# Hitachi100NZ.net
KiCad netlist of a schematic drawn in Altium Designer
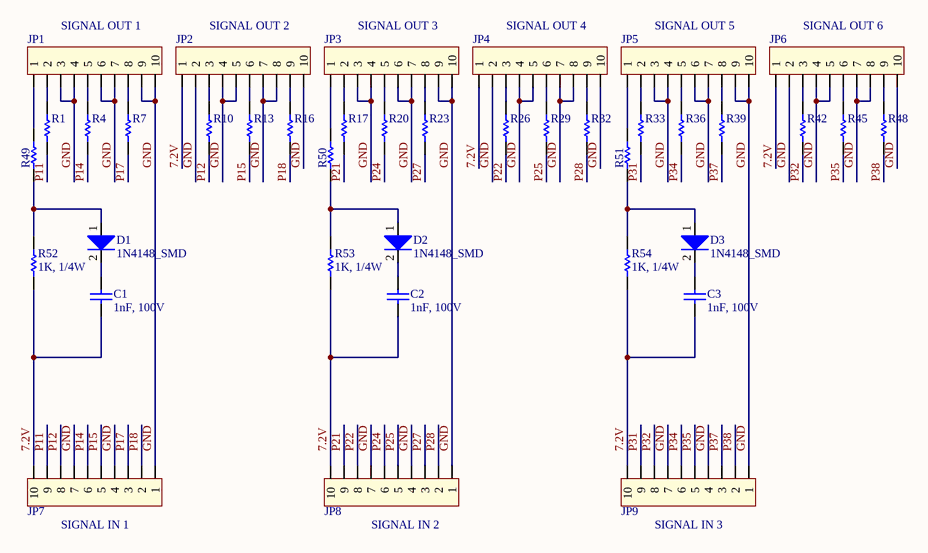
[diagram p0: Hitachi100NZ.SchDoc]

(export (version "E")
  (design (tool "Eeschema 10.0.6"))
  (components
    (comp (ref "C1")
      (value "1nF, 100V")
      (footprint "C0603")
      (description "CAP NPO CAPNTO 1nF 100V 10%")
      (fields (field (name "Comment") "5AK102KABAA"))
      (libsource (lib "lpson") (part "5AK102KABAA"))
    )
    (comp (ref "C2")
      (value "1nF, 100V")
      (footprint "C0603")
      (description "CAP NPO CAPNTO 1nF 100V 10%")
      (fields (field (name "Comment") "5AK102KABAA"))
      (libsource (lib "lpson") (part "5AK102KABAA"))
    )
    (comp (ref "C3")
      (value "1nF, 100V")
      (footprint "C0603")
      (description "CAP NPO CAPNTO 1nF 100V 10%")
      (fields (field (name "Comment") "5AK102KABAA"))
      (libsource (lib "lpson") (part "5AK102KABAA"))
    )
    (comp (ref "D1")
      (value "1N4148_SMD")
      (footprint "1N4148W_V_SMD")
      (description "Diode HS 500mA 100V SOD123")
      (libsource (lib "lpson") (part "1N4148_SMD"))
    )
    (comp (ref "D2")
      (value "1N4148_SMD")
      (footprint "1N4148W_V_SMD")
      (description "Diode HS 500mA 100V SOD123")
      (libsource (lib "lpson") (part "1N4148_SMD"))
    )
    (comp (ref "D3")
      (value "1N4148_SMD")
      (footprint "1N4148W_V_SMD")
      (description "Diode HS 500mA 100V SOD123")
      (libsource (lib "lpson") (part "1N4148_SMD"))
    )
    (comp (ref "JP1")
      (value "SIGNAL OUT 1")
      (footprint "HeaderSP_5x2")
      (description "Connector 10")
      (libsource (lib "") (part "Con10_1"))
    )
    (comp (ref "JP2")
      (value "SIGNAL OUT 2")
      (footprint "HeaderSP_5x2")
      (description "Connector 10")
      (libsource (lib "") (part "Con10_1"))
    )
    (comp (ref "JP3")
      (value "SIGNAL OUT 3")
      (footprint "HeaderSP_5x2")
      (description "Connector 10")
      (libsource (lib "") (part "Con10_1"))
    )
    (comp (ref "JP4")
      (value "SIGNAL OUT 4")
      (footprint "HeaderSP_5x2")
      (description "Connector 10")
      (libsource (lib "") (part "Con10_1"))
    )
    (comp (ref "JP5")
      (value "SIGNAL OUT 5")
      (footprint "HeaderSP_5x2")
      (description "Connector 10")
      (libsource (lib "") (part "Con10_1"))
    )
    (comp (ref "JP6")
      (value "SIGNAL OUT 6")
      (footprint "HeaderSP_5x2")
      (description "Connector 10")
      (libsource (lib "") (part "Con10_1"))
    )
    (comp (ref "JP7")
      (value "SIGNAL IN 1")
      (footprint "HeaderSP_5x2")
      (description "Connector 10")
      (libsource (lib "lpson") (part "Con10"))
    )
    (comp (ref "JP8")
      (value "SIGNAL IN 2")
      (footprint "HeaderSP_5x2")
      (description "Connector 10")
      (libsource (lib "lpson") (part "Con10"))
    )
    (comp (ref "JP9")
      (value "SIGNAL IN 3")
      (footprint "HeaderSP_5x2")
      (description "Connector 10")
      (libsource (lib "lpson") (part "Con10"))
    )
    (comp (ref "R1")
      (value "CF1/4W1KJ25")
      (footprint "RM06JTN (0603)")
      (description "RES CF AXIAL-0.3 5% 1/4W 1K")
      (libsource (lib "lpson") (part "CF1/4W1KJ25"))
    )
    (comp (ref "R4")
      (value "CF1/4W1KJ25")
      (footprint "RM06JTN (0603)")
      (description "RES CF AXIAL-0.3 5% 1/4W 1K")
      (libsource (lib "lpson") (part "CF1/4W1KJ25"))
    )
    (comp (ref "R7")
      (value "CF1/4W1KJ25")
      (footprint "RM06JTN (0603)")
      (description "RES CF AXIAL-0.3 5% 1/4W 1K")
      (libsource (lib "lpson") (part "CF1/4W1KJ25"))
    )
    (comp (ref "R10")
      (value "CF1/4W1KJ25")
      (footprint "RM06JTN (0603)")
      (description "RES CF AXIAL-0.3 5% 1/4W 1K")
      (libsource (lib "lpson") (part "CF1/4W1KJ25"))
    )
    (comp (ref "R13")
      (value "CF1/4W1KJ25")
      (footprint "RM06JTN (0603)")
      (description "RES CF AXIAL-0.3 5% 1/4W 1K")
      (libsource (lib "lpson") (part "CF1/4W1KJ25"))
    )
    (comp (ref "R16")
      (value "CF1/4W1KJ25")
      (footprint "RM06JTN (0603)")
      (description "RES CF AXIAL-0.3 5% 1/4W 1K")
      (libsource (lib "lpson") (part "CF1/4W1KJ25"))
    )
    (comp (ref "R17")
      (value "CF1/4W1KJ25")
      (footprint "RM06JTN (0603)")
      (description "RES CF AXIAL-0.3 5% 1/4W 1K")
      (libsource (lib "lpson") (part "CF1/4W1KJ25"))
    )
    (comp (ref "R20")
      (value "CF1/4W1KJ25")
      (footprint "RM06JTN (0603)")
      (description "RES CF AXIAL-0.3 5% 1/4W 1K")
      (libsource (lib "lpson") (part "CF1/4W1KJ25"))
    )
    (comp (ref "R23")
      (value "CF1/4W1KJ25")
      (footprint "RM06JTN (0603)")
      (description "RES CF AXIAL-0.3 5% 1/4W 1K")
      (libsource (lib "lpson") (part "CF1/4W1KJ25"))
    )
    (comp (ref "R26")
      (value "CF1/4W1KJ25")
      (footprint "RM06JTN (0603)")
      (description "RES CF AXIAL-0.3 5% 1/4W 1K")
      (libsource (lib "lpson") (part "CF1/4W1KJ25"))
    )
    (comp (ref "R29")
      (value "CF1/4W1KJ25")
      (footprint "RM06JTN (0603)")
      (description "RES CF AXIAL-0.3 5% 1/4W 1K")
      (libsource (lib "lpson") (part "CF1/4W1KJ25"))
    )
    (comp (ref "R32")
      (value "CF1/4W1KJ25")
      (footprint "RM06JTN (0603)")
      (description "RES CF AXIAL-0.3 5% 1/4W 1K")
      (libsource (lib "lpson") (part "CF1/4W1KJ25"))
    )
    (comp (ref "R33")
      (value "CF1/4W1KJ25")
      (footprint "RM06JTN (0603)")
      (description "RES CF AXIAL-0.3 5% 1/4W 1K")
      (libsource (lib "lpson") (part "CF1/4W1KJ25"))
    )
    (comp (ref "R36")
      (value "CF1/4W1KJ25")
      (footprint "RM06JTN (0603)")
      (description "RES CF AXIAL-0.3 5% 1/4W 1K")
      (libsource (lib "lpson") (part "CF1/4W1KJ25"))
    )
    (comp (ref "R39")
      (value "CF1/4W1KJ25")
      (footprint "RM06JTN (0603)")
      (description "RES CF AXIAL-0.3 5% 1/4W 1K")
      (libsource (lib "lpson") (part "CF1/4W1KJ25"))
    )
    (comp (ref "R42")
      (value "CF1/4W1KJ25")
      (footprint "RM06JTN (0603)")
      (description "RES CF AXIAL-0.3 5% 1/4W 1K")
      (libsource (lib "lpson") (part "CF1/4W1KJ25"))
    )
    (comp (ref "R45")
      (value "CF1/4W1KJ25")
      (footprint "RM06JTN (0603)")
      (description "RES CF AXIAL-0.3 5% 1/4W 1K")
      (libsource (lib "lpson") (part "CF1/4W1KJ25"))
    )
    (comp (ref "R48")
      (value "CF1/4W1KJ25")
      (footprint "RM06JTN (0603)")
      (description "RES CF AXIAL-0.3 5% 1/4W 1K")
      (libsource (lib "lpson") (part "CF1/4W1KJ25"))
    )
    (comp (ref "R49")
      (value "CF1/4W1KJ25")
      (footprint "RM06JTN (0603)")
      (description "RES CF AXIAL-0.3 5% 1/4W 1K")
      (libsource (lib "lpson") (part "CF1/4W1KJ25"))
    )
    (comp (ref "R50")
      (value "CF1/4W1KJ25")
      (footprint "RM06JTN (0603)")
      (description "RES CF AXIAL-0.3 5% 1/4W 1K")
      (libsource (lib "lpson") (part "CF1/4W1KJ25"))
    )
    (comp (ref "R51")
      (value "CF1/4W1KJ25")
      (footprint "RM06JTN (0603)")
      (description "RES CF AXIAL-0.3 5% 1/4W 1K")
      (libsource (lib "lpson") (part "CF1/4W1KJ25"))
    )
    (comp (ref "R52")
      (value "1K, 1/4W")
      (footprint "RM06JTN (0603)")
      (description "RES CF AXIAL-0.3 5% 1/4W 1K")
      (fields (field (name "Comment") "CF1/4W1KJ25"))
      (libsource (lib "lpson") (part "CF1/4W1KJ25"))
    )
    (comp (ref "R53")
      (value "1K, 1/4W")
      (footprint "RM06JTN (0603)")
      (description "RES CF AXIAL-0.3 5% 1/4W 1K")
      (fields (field (name "Comment") "CF1/4W1KJ25"))
      (libsource (lib "lpson") (part "CF1/4W1KJ25"))
    )
    (comp (ref "R54")
      (value "1K, 1/4W")
      (footprint "RM06JTN (0603)")
      (description "RES CF AXIAL-0.3 5% 1/4W 1K")
      (fields (field (name "Comment") "CF1/4W1KJ25"))
      (libsource (lib "lpson") (part "CF1/4W1KJ25"))
    )
  )
  (nets
    (net (code "1") (name "/7.2V") (class "Default")
      (node (ref "C1") (pin "1") (pinfunction "1_1") (pintype "passive"))
      (node (ref "C2") (pin "1") (pinfunction "1_1") (pintype "passive"))
      (node (ref "C3") (pin "1") (pinfunction "1_1") (pintype "passive"))
      (node (ref "JP2") (pin "1") (pinfunction "1_1") (pintype "passive"))
      (node (ref "JP4") (pin "1") (pinfunction "1_1") (pintype "passive"))
      (node (ref "JP6") (pin "1") (pinfunction "1_1") (pintype "passive"))
      (node (ref "JP7") (pin "10") (pinfunction "10_10") (pintype "passive"))
      (node (ref "JP8") (pin "10") (pinfunction "10_10") (pintype "passive"))
      (node (ref "JP9") (pin "10") (pinfunction "10_10") (pintype "passive"))
      (node (ref "R52") (pin "1") (pinfunction "1_1") (pintype "passive"))
      (node (ref "R53") (pin "1") (pinfunction "1_1") (pintype "passive"))
      (node (ref "R54") (pin "1") (pinfunction "1_1") (pintype "passive"))
    )
    (net (code "2") (name "/GND") (class "Default")
      (node (ref "JP1") (pin "10") (pinfunction "10_10") (pintype "passive"))
      (node (ref "JP1") (pin "3") (pinfunction "3_3") (pintype "passive"))
      (node (ref "JP1") (pin "4") (pinfunction "4_4") (pintype "passive"))
      (node (ref "JP1") (pin "6") (pinfunction "6_6") (pintype "passive"))
      (node (ref "JP1") (pin "7") (pinfunction "7_7") (pintype "passive"))
      (node (ref "JP1") (pin "9") (pinfunction "9_9") (pintype "passive"))
      (node (ref "JP2") (pin "10") (pinfunction "10_10") (pintype "passive"))
      (node (ref "JP2") (pin "2") (pinfunction "2_2") (pintype "passive"))
      (node (ref "JP2") (pin "4") (pinfunction "4_4") (pintype "passive"))
      (node (ref "JP2") (pin "5") (pinfunction "5_5") (pintype "passive"))
      (node (ref "JP2") (pin "7") (pinfunction "7_7") (pintype "passive"))
      (node (ref "JP2") (pin "8") (pinfunction "8_8") (pintype "passive"))
      (node (ref "JP3") (pin "10") (pinfunction "10_10") (pintype "passive"))
      (node (ref "JP3") (pin "3") (pinfunction "3_3") (pintype "passive"))
      (node (ref "JP3") (pin "4") (pinfunction "4_4") (pintype "passive"))
      (node (ref "JP3") (pin "6") (pinfunction "6_6") (pintype "passive"))
      (node (ref "JP3") (pin "7") (pinfunction "7_7") (pintype "passive"))
      (node (ref "JP3") (pin "9") (pinfunction "9_9") (pintype "passive"))
      (node (ref "JP4") (pin "10") (pinfunction "10_10") (pintype "passive"))
      (node (ref "JP4") (pin "2") (pinfunction "2_2") (pintype "passive"))
      (node (ref "JP4") (pin "4") (pinfunction "4_4") (pintype "passive"))
      (node (ref "JP4") (pin "5") (pinfunction "5_5") (pintype "passive"))
      (node (ref "JP4") (pin "7") (pinfunction "7_7") (pintype "passive"))
      (node (ref "JP4") (pin "8") (pinfunction "8_8") (pintype "passive"))
      (node (ref "JP5") (pin "10") (pinfunction "10_10") (pintype "passive"))
      (node (ref "JP5") (pin "3") (pinfunction "3_3") (pintype "passive"))
      (node (ref "JP5") (pin "4") (pinfunction "4_4") (pintype "passive"))
      (node (ref "JP5") (pin "6") (pinfunction "6_6") (pintype "passive"))
      (node (ref "JP5") (pin "7") (pinfunction "7_7") (pintype "passive"))
      (node (ref "JP5") (pin "9") (pinfunction "9_9") (pintype "passive"))
      (node (ref "JP6") (pin "10") (pinfunction "10_10") (pintype "passive"))
      (node (ref "JP6") (pin "2") (pinfunction "2_2") (pintype "passive"))
      (node (ref "JP6") (pin "4") (pinfunction "4_4") (pintype "passive"))
      (node (ref "JP6") (pin "5") (pinfunction "5_5") (pintype "passive"))
      (node (ref "JP6") (pin "7") (pinfunction "7_7") (pintype "passive"))
      (node (ref "JP6") (pin "8") (pinfunction "8_8") (pintype "passive"))
      (node (ref "JP7") (pin "1") (pinfunction "1_1") (pintype "passive"))
      (node (ref "JP7") (pin "4") (pinfunction "4_4") (pintype "passive"))
      (node (ref "JP7") (pin "7") (pinfunction "7_7") (pintype "passive"))
      (node (ref "JP8") (pin "1") (pinfunction "1_1") (pintype "passive"))
      (node (ref "JP8") (pin "4") (pinfunction "4_4") (pintype "passive"))
      (node (ref "JP8") (pin "7") (pinfunction "7_7") (pintype "passive"))
      (node (ref "JP9") (pin "1") (pinfunction "1_1") (pintype "passive"))
      (node (ref "JP9") (pin "4") (pinfunction "4_4") (pintype "passive"))
      (node (ref "JP9") (pin "7") (pinfunction "7_7") (pintype "passive"))
    )
    (net (code "3") (name "/P11") (class "Default")
      (node (ref "JP7") (pin "9") (pinfunction "9_9") (pintype "passive"))
      (node (ref "R1") (pin "1") (pinfunction "1_1") (pintype "passive"))
    )
    (net (code "4") (name "/P12") (class "Default")
      (node (ref "JP7") (pin "8") (pinfunction "8_8") (pintype "passive"))
      (node (ref "R10") (pin "1") (pinfunction "1_1") (pintype "passive"))
    )
    (net (code "5") (name "/P14") (class "Default")
      (node (ref "JP7") (pin "6") (pinfunction "6_6") (pintype "passive"))
      (node (ref "R4") (pin "1") (pinfunction "1_1") (pintype "passive"))
    )
    (net (code "6") (name "/P15") (class "Default")
      (node (ref "JP7") (pin "5") (pinfunction "5_5") (pintype "passive"))
      (node (ref "R13") (pin "1") (pinfunction "1_1") (pintype "passive"))
    )
    (net (code "7") (name "/P17") (class "Default")
      (node (ref "JP7") (pin "3") (pinfunction "3_3") (pintype "passive"))
      (node (ref "R7") (pin "1") (pinfunction "1_1") (pintype "passive"))
    )
    (net (code "8") (name "/P18") (class "Default")
      (node (ref "JP7") (pin "2") (pinfunction "2_2") (pintype "passive"))
      (node (ref "R16") (pin "1") (pinfunction "1_1") (pintype "passive"))
    )
    (net (code "9") (name "/P21") (class "Default")
      (node (ref "JP8") (pin "9") (pinfunction "9_9") (pintype "passive"))
      (node (ref "R17") (pin "1") (pinfunction "1_1") (pintype "passive"))
    )
    (net (code "10") (name "/P22") (class "Default")
      (node (ref "JP8") (pin "8") (pinfunction "8_8") (pintype "passive"))
      (node (ref "R26") (pin "1") (pinfunction "1_1") (pintype "passive"))
    )
    (net (code "11") (name "/P24") (class "Default")
      (node (ref "JP8") (pin "6") (pinfunction "6_6") (pintype "passive"))
      (node (ref "R20") (pin "1") (pinfunction "1_1") (pintype "passive"))
    )
    (net (code "12") (name "/P25") (class "Default")
      (node (ref "JP8") (pin "5") (pinfunction "5_5") (pintype "passive"))
      (node (ref "R29") (pin "1") (pinfunction "1_1") (pintype "passive"))
    )
    (net (code "13") (name "/P27") (class "Default")
      (node (ref "JP8") (pin "3") (pinfunction "3_3") (pintype "passive"))
      (node (ref "R23") (pin "1") (pinfunction "1_1") (pintype "passive"))
    )
    (net (code "14") (name "/P28") (class "Default")
      (node (ref "JP8") (pin "2") (pinfunction "2_2") (pintype "passive"))
      (node (ref "R32") (pin "1") (pinfunction "1_1") (pintype "passive"))
    )
    (net (code "15") (name "/P31") (class "Default")
      (node (ref "JP9") (pin "9") (pinfunction "9_9") (pintype "passive"))
      (node (ref "R33") (pin "1") (pinfunction "1_1") (pintype "passive"))
    )
    (net (code "16") (name "/P32") (class "Default")
      (node (ref "JP9") (pin "8") (pinfunction "8_8") (pintype "passive"))
      (node (ref "R42") (pin "1") (pinfunction "1_1") (pintype "passive"))
    )
    (net (code "17") (name "/P34") (class "Default")
      (node (ref "JP9") (pin "6") (pinfunction "6_6") (pintype "passive"))
      (node (ref "R36") (pin "1") (pinfunction "1_1") (pintype "passive"))
    )
    (net (code "18") (name "/P35") (class "Default")
      (node (ref "JP9") (pin "5") (pinfunction "5_5") (pintype "passive"))
      (node (ref "R45") (pin "1") (pinfunction "1_1") (pintype "passive"))
    )
    (net (code "19") (name "/P37") (class "Default")
      (node (ref "JP9") (pin "3") (pinfunction "3_3") (pintype "passive"))
      (node (ref "R39") (pin "1") (pinfunction "1_1") (pintype "passive"))
    )
    (net (code "20") (name "/P38") (class "Default")
      (node (ref "JP9") (pin "2") (pinfunction "2_2") (pintype "passive"))
      (node (ref "R48") (pin "1") (pinfunction "1_1") (pintype "passive"))
    )
    (net (code "21") (name "Net-(D1-A)") (class "Default")
      (node (ref "D1") (pin "1") (pinfunction "A_1") (pintype "passive"))
      (node (ref "R49") (pin "1") (pinfunction "1_1") (pintype "passive"))
      (node (ref "R52") (pin "2") (pinfunction "2_2") (pintype "passive"))
    )
    (net (code "22") (name "Net-(D1-K)") (class "Default")
      (node (ref "C1") (pin "2") (pinfunction "2_2") (pintype "passive"))
      (node (ref "D1") (pin "2") (pinfunction "K_2") (pintype "passive"))
    )
    (net (code "23") (name "Net-(D2-A)") (class "Default")
      (node (ref "D2") (pin "1") (pinfunction "A_1") (pintype "passive"))
      (node (ref "R50") (pin "1") (pinfunction "1_1") (pintype "passive"))
      (node (ref "R53") (pin "2") (pinfunction "2_2") (pintype "passive"))
    )
    (net (code "24") (name "Net-(D2-K)") (class "Default")
      (node (ref "C2") (pin "2") (pinfunction "2_2") (pintype "passive"))
      (node (ref "D2") (pin "2") (pinfunction "K_2") (pintype "passive"))
    )
    (net (code "25") (name "Net-(D3-A)") (class "Default")
      (node (ref "D3") (pin "1") (pinfunction "A_1") (pintype "passive"))
      (node (ref "R51") (pin "1") (pinfunction "1_1") (pintype "passive"))
      (node (ref "R54") (pin "2") (pinfunction "2_2") (pintype "passive"))
    )
    (net (code "26") (name "Net-(D3-K)") (class "Default")
      (node (ref "C3") (pin "2") (pinfunction "2_2") (pintype "passive"))
      (node (ref "D3") (pin "2") (pinfunction "K_2") (pintype "passive"))
    )
    (net (code "27") (name "Net-(JP1-Pad1)") (class "Default")
      (node (ref "JP1") (pin "1") (pinfunction "1_1") (pintype "passive"))
      (node (ref "R49") (pin "2") (pinfunction "2_2") (pintype "passive"))
    )
    (net (code "28") (name "Net-(JP1-Pad2)") (class "Default")
      (node (ref "JP1") (pin "2") (pinfunction "2_2") (pintype "passive"))
      (node (ref "R1") (pin "2") (pinfunction "2_2") (pintype "passive"))
    )
    (net (code "29") (name "Net-(JP1-Pad5)") (class "Default")
      (node (ref "JP1") (pin "5") (pinfunction "5_5") (pintype "passive"))
      (node (ref "R4") (pin "2") (pinfunction "2_2") (pintype "passive"))
    )
    (net (code "30") (name "Net-(JP1-Pad8)") (class "Default")
      (node (ref "JP1") (pin "8") (pinfunction "8_8") (pintype "passive"))
      (node (ref "R7") (pin "2") (pinfunction "2_2") (pintype "passive"))
    )
    (net (code "31") (name "Net-(JP2-Pad3)") (class "Default")
      (node (ref "JP2") (pin "3") (pinfunction "3_3") (pintype "passive"))
      (node (ref "R10") (pin "2") (pinfunction "2_2") (pintype "passive"))
    )
    (net (code "32") (name "Net-(JP2-Pad6)") (class "Default")
      (node (ref "JP2") (pin "6") (pinfunction "6_6") (pintype "passive"))
      (node (ref "R13") (pin "2") (pinfunction "2_2") (pintype "passive"))
    )
    (net (code "33") (name "Net-(JP2-Pad9)") (class "Default")
      (node (ref "JP2") (pin "9") (pinfunction "9_9") (pintype "passive"))
      (node (ref "R16") (pin "2") (pinfunction "2_2") (pintype "passive"))
    )
    (net (code "34") (name "Net-(JP3-Pad1)") (class "Default")
      (node (ref "JP3") (pin "1") (pinfunction "1_1") (pintype "passive"))
      (node (ref "R50") (pin "2") (pinfunction "2_2") (pintype "passive"))
    )
    (net (code "35") (name "Net-(JP3-Pad2)") (class "Default")
      (node (ref "JP3") (pin "2") (pinfunction "2_2") (pintype "passive"))
      (node (ref "R17") (pin "2") (pinfunction "2_2") (pintype "passive"))
    )
    (net (code "36") (name "Net-(JP3-Pad5)") (class "Default")
      (node (ref "JP3") (pin "5") (pinfunction "5_5") (pintype "passive"))
      (node (ref "R20") (pin "2") (pinfunction "2_2") (pintype "passive"))
    )
    (net (code "37") (name "Net-(JP3-Pad8)") (class "Default")
      (node (ref "JP3") (pin "8") (pinfunction "8_8") (pintype "passive"))
      (node (ref "R23") (pin "2") (pinfunction "2_2") (pintype "passive"))
    )
    (net (code "38") (name "Net-(JP4-Pad3)") (class "Default")
      (node (ref "JP4") (pin "3") (pinfunction "3_3") (pintype "passive"))
      (node (ref "R26") (pin "2") (pinfunction "2_2") (pintype "passive"))
    )
    (net (code "39") (name "Net-(JP4-Pad6)") (class "Default")
      (node (ref "JP4") (pin "6") (pinfunction "6_6") (pintype "passive"))
      (node (ref "R29") (pin "2") (pinfunction "2_2") (pintype "passive"))
    )
    (net (code "40") (name "Net-(JP4-Pad9)") (class "Default")
      (node (ref "JP4") (pin "9") (pinfunction "9_9") (pintype "passive"))
      (node (ref "R32") (pin "2") (pinfunction "2_2") (pintype "passive"))
    )
    (net (code "41") (name "Net-(JP5-Pad1)") (class "Default")
      (node (ref "JP5") (pin "1") (pinfunction "1_1") (pintype "passive"))
      (node (ref "R51") (pin "2") (pinfunction "2_2") (pintype "passive"))
    )
    (net (code "42") (name "Net-(JP5-Pad2)") (class "Default")
      (node (ref "JP5") (pin "2") (pinfunction "2_2") (pintype "passive"))
      (node (ref "R33") (pin "2") (pinfunction "2_2") (pintype "passive"))
    )
    (net (code "43") (name "Net-(JP5-Pad5)") (class "Default")
      (node (ref "JP5") (pin "5") (pinfunction "5_5") (pintype "passive"))
      (node (ref "R36") (pin "2") (pinfunction "2_2") (pintype "passive"))
    )
    (net (code "44") (name "Net-(JP5-Pad8)") (class "Default")
      (node (ref "JP5") (pin "8") (pinfunction "8_8") (pintype "passive"))
      (node (ref "R39") (pin "2") (pinfunction "2_2") (pintype "passive"))
    )
    (net (code "45") (name "Net-(JP6-Pad3)") (class "Default")
      (node (ref "JP6") (pin "3") (pinfunction "3_3") (pintype "passive"))
      (node (ref "R42") (pin "2") (pinfunction "2_2") (pintype "passive"))
    )
    (net (code "46") (name "Net-(JP6-Pad6)") (class "Default")
      (node (ref "JP6") (pin "6") (pinfunction "6_6") (pintype "passive"))
      (node (ref "R45") (pin "2") (pinfunction "2_2") (pintype "passive"))
    )
    (net (code "47") (name "Net-(JP6-Pad9)") (class "Default")
      (node (ref "JP6") (pin "9") (pinfunction "9_9") (pintype "passive"))
      (node (ref "R48") (pin "2") (pinfunction "2_2") (pintype "passive"))
    )
  )
)
